# pic.net
KiCad netlist of a schematic drawn in Altium Designer
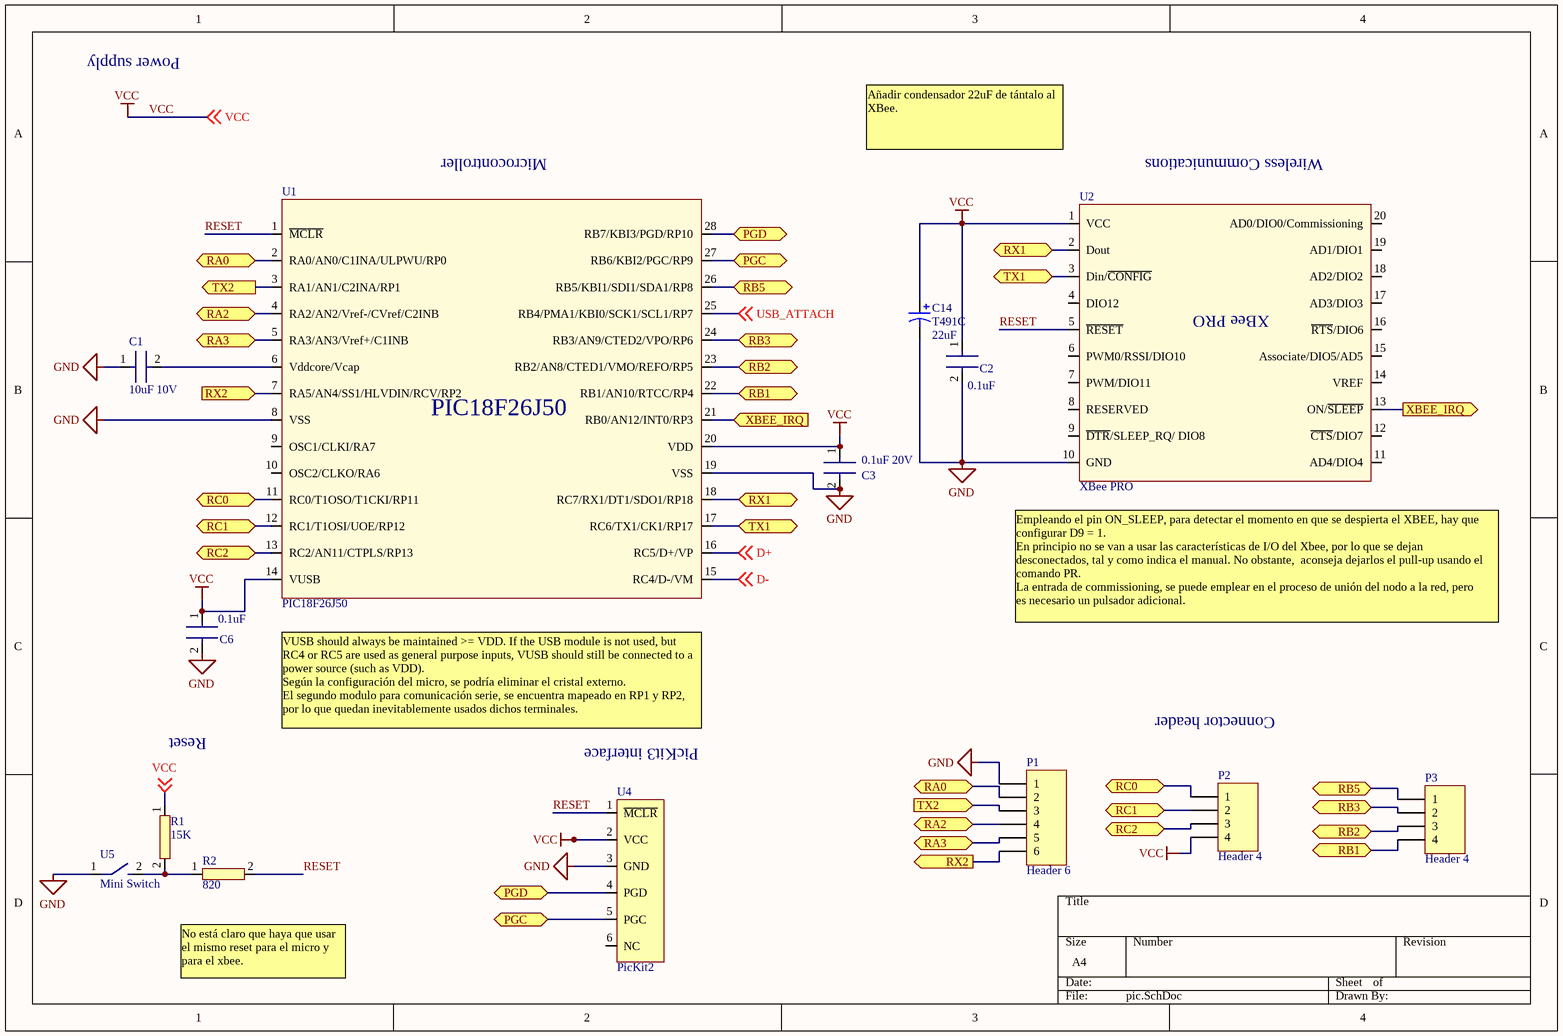
[diagram p0: pic.SchDoc]

(export (version "E")
  (design (tool "Eeschema 10.0.6"))
  (components
    (comp (ref "C1")
      (value "10uF 10V")
      (footprint "C1206")
      (libsource (lib "uMote") (part "TDK C3216X7R1C106K"))
    )
    (comp (ref "C2")
      (value "0.1uF")
      (footprint "C1206")
      (libsource (lib "uMote") (part "TDK C3216X7R1C106K"))
    )
    (comp (ref "C3")
      (value "0.1uF 20V")
      (footprint "C1206")
      (libsource (lib "uMote") (part "TDK C3216X7R1C106K"))
    )
    (comp (ref "C6")
      (value "0.1uF")
      (footprint "C1206")
      (libsource (lib "uMote") (part "TDK C3216X7R1C106K"))
    )
    (comp (ref "C14")
      (value "T491C")
      (footprint "C")
      (description "Solid Tantalum Chip Capacitor, Standard T491 Series - Industrial Grade")
      (fields (field (name "ALTIUM_VALUE") "22uF") (field (name "PUBLISHER") "Altium Limited"))
      (libsource (lib "KEMET Chip Capacitor") (part "T491C"))
    )
    (comp (ref "P1")
      (value "Header 6")
      (footprint "HDR1X6")
      (description "Header, 6-Pin")
      (fields (field (name "PUBLISHER") "Altium Limited"))
      (libsource (lib "Miscellaneous Connectors") (part "Header 6"))
    )
    (comp (ref "P2")
      (value "Header 4")
      (footprint "HDR1X4")
      (description "Header, 4-Pin")
      (fields (field (name "PUBLISHER") "Altium Limited"))
      (libsource (lib "Miscellaneous Connectors") (part "Header 4"))
    )
    (comp (ref "P3")
      (value "Header 4")
      (footprint "HDR1X4")
      (description "Header, 4-Pin")
      (fields (field (name "PUBLISHER") "Altium Limited"))
      (libsource (lib "Miscellaneous Connectors") (part "Header 4"))
    )
    (comp (ref "R1") (value "15K") (footprint "3216[1206]") (libsource (lib "uMote") (part "RES 1206")))
    (comp (ref "R2") (value "820") (footprint "3216[1206]") (libsource (lib "") (part "RES 1206_1")))
    (comp (ref "U1")
      (value "PIC18F26J50")
      (footprint "PIC18F-SOIC")
      (libsource (lib "uMote") (part "PIC18F26J50"))
    )
    (comp (ref "U2") (value "XBee PRO") (footprint "XBee PRO") (libsource (lib "uMote") (part "XBee PRO")))
    (comp (ref "U4") (value "PicKit2") (footprint "PICKIT3") (libsource (lib "uMote") (part "PicKit2")))
    (comp (ref "U5")
      (value "Mini Switch")
      (footprint "Mini Switch")
      (libsource (lib "uMote") (part "Mini Switch"))
    )
  )
  (nets
    (net (code "1") (name "/PGC") (class "Default")
      (node (ref "U1") (pin "27") (pinfunction "RB6/KBI2/PGC/RP9_27") (pintype "passive"))
      (node (ref "U4") (pin "5") (pinfunction "PGC_5") (pintype "passive"))
    )
    (net (code "2") (name "/PGD") (class "Default")
      (node (ref "U1") (pin "28") (pinfunction "RB7/KBI3/PGD/RP10_28") (pintype "passive"))
      (node (ref "U4") (pin "4") (pinfunction "PGD_4") (pintype "passive"))
    )
    (net (code "3") (name "/RA0") (class "Default")
      (node (ref "P1") (pin "2") (pinfunction "2_2") (pintype "passive"))
      (node (ref "U1") (pin "2") (pinfunction "RA0/AN0/C1INA/ULPWU/RP0_2") (pintype "passive"))
    )
    (net (code "4") (name "/RA2") (class "Default")
      (node (ref "P1") (pin "4") (pinfunction "4_4") (pintype "passive"))
      (node (ref "U1") (pin "4") (pinfunction "RA2/AN2/Vref-/CVref/C2INB_4") (pintype "passive"))
    )
    (net (code "5") (name "/RA3") (class "Default")
      (node (ref "P1") (pin "5") (pinfunction "5_5") (pintype "passive"))
      (node (ref "U1") (pin "5") (pinfunction "RA3/AN3/Vref+/C1INB_5") (pintype "passive"))
    )
    (net (code "6") (name "/RB1") (class "Default")
      (node (ref "P3") (pin "4") (pinfunction "4_4") (pintype "passive"))
      (node (ref "U1") (pin "22") (pinfunction "RB1/AN10/RTCC/RP4_22") (pintype "passive"))
    )
    (net (code "7") (name "/RB2") (class "Default")
      (node (ref "P3") (pin "3") (pinfunction "3_3") (pintype "passive"))
      (node (ref "U1") (pin "23") (pinfunction "RB2/AN8/CTED1/VMO/REFO/RP5_23") (pintype "passive"))
    )
    (net (code "8") (name "/RB3") (class "Default")
      (node (ref "P3") (pin "2") (pinfunction "2_2") (pintype "passive"))
      (node (ref "U1") (pin "24") (pinfunction "RB3/AN9/CTED2/VPO/RP6_24") (pintype "passive"))
    )
    (net (code "9") (name "/RB5") (class "Default")
      (node (ref "P3") (pin "1") (pinfunction "1_1") (pintype "passive"))
      (node (ref "U1") (pin "26") (pinfunction "RB5/KBI1/SDI1/SDA1/RP8_26") (pintype "passive"))
    )
    (net (code "10") (name "/RC0") (class "Default")
      (node (ref "P2") (pin "1") (pinfunction "1_1") (pintype "passive"))
      (node (ref "U1") (pin "11") (pinfunction "RC0/T1OSO/T1CKI/RP11_11") (pintype "passive"))
    )
    (net (code "11") (name "/RC1") (class "Default")
      (node (ref "P2") (pin "2") (pinfunction "2_2") (pintype "passive"))
      (node (ref "U1") (pin "12") (pinfunction "RC1/T1OSI/UOE/RP12_12") (pintype "passive"))
    )
    (net (code "12") (name "/RC2") (class "Default")
      (node (ref "P2") (pin "3") (pinfunction "3_3") (pintype "passive"))
      (node (ref "U1") (pin "13") (pinfunction "RC2/AN11/CTPLS/RP13_13") (pintype "passive"))
    )
    (net (code "13") (name "/RESET") (class "Default")
      (node (ref "R2") (pin "2") (pinfunction "2_2") (pintype "passive"))
      (node (ref "U1") (pin "1") (pinfunction "MCLR_1") (pintype "input"))
      (node (ref "U2") (pin "5") (pinfunction "RESET_5") (pintype "passive"))
      (node (ref "U4") (pin "1") (pinfunction "MCLR_1") (pintype "passive"))
    )
    (net (code "14") (name "/RX1") (class "Default")
      (node (ref "U1") (pin "18") (pinfunction "RC7/RX1/DT1/SDO1/RP18_18") (pintype "passive"))
      (node (ref "U2") (pin "2") (pinfunction "Dout_2") (pintype "passive"))
    )
    (net (code "15") (name "/RX2") (class "Default")
      (node (ref "P1") (pin "6") (pinfunction "6_6") (pintype "passive"))
      (node (ref "U1") (pin "7") (pinfunction "RA5/AN4/SS1/HLVDIN/RCV/RP2_7") (pintype "passive"))
    )
    (net (code "16") (name "/TX1") (class "Default")
      (node (ref "U1") (pin "17") (pinfunction "RC6/TX1/CK1/RP17_17") (pintype "passive"))
      (node (ref "U2") (pin "3") (pinfunction "Din/~{CONFIG}_3") (pintype "passive"))
    )
    (net (code "17") (name "/TX2") (class "Default")
      (node (ref "P1") (pin "3") (pinfunction "3_3") (pintype "passive"))
      (node (ref "U1") (pin "3") (pinfunction "RA1/AN1/C2INA/RP1_3") (pintype "passive"))
    )
    (net (code "18") (name "/XBEE_IRQ") (class "Default")
      (node (ref "U1") (pin "21") (pinfunction "RB0/AN12/INT0/RP3_21") (pintype "passive"))
      (node (ref "U2") (pin "13") (pinfunction "ON/~{SLEEP}_13") (pintype "passive"))
    )
    (net (code "19") (name "D+") (class "Default")
      (node (ref "U1") (pin "16") (pinfunction "RC5/D+/VP_16") (pintype "passive"))
    )
    (net (code "20") (name "D-") (class "Default")
      (node (ref "U1") (pin "15") (pinfunction "RC4/D-/VM_15") (pintype "passive"))
    )
    (net (code "21") (name "GND") (class "Default")
      (node (ref "C1") (pin "1") (pinfunction "1_1") (pintype "passive"))
      (node (ref "C14") (pin "2") (pinfunction "2_2") (pintype "passive"))
      (node (ref "C2") (pin "2") (pinfunction "2_2") (pintype "passive"))
      (node (ref "C3") (pin "2") (pinfunction "2_2") (pintype "passive"))
      (node (ref "C6") (pin "2") (pinfunction "2_2") (pintype "passive"))
      (node (ref "P1") (pin "1") (pinfunction "1_1") (pintype "passive"))
      (node (ref "U1") (pin "19") (pinfunction "VSS_19") (pintype "passive"))
      (node (ref "U1") (pin "8") (pinfunction "VSS_8") (pintype "passive"))
      (node (ref "U2") (pin "10") (pinfunction "GND_10") (pintype "passive"))
      (node (ref "U4") (pin "3") (pinfunction "GND_3") (pintype "passive"))
      (node (ref "U5") (pin "1") (pinfunction "1_1") (pintype "passive"))
    )
    (net (code "22") (name "Net-(R1-Pad2)") (class "Default")
      (node (ref "R1") (pin "2") (pinfunction "2_2") (pintype "passive"))
      (node (ref "R2") (pin "1") (pinfunction "1_1") (pintype "passive"))
      (node (ref "U5") (pin "2") (pinfunction "2_2") (pintype "passive"))
    )
    (net (code "23") (name "Net-(U1-Vddcore{slash}Vcap)") (class "Default")
      (node (ref "C1") (pin "2") (pinfunction "2_2") (pintype "passive"))
      (node (ref "U1") (pin "6") (pinfunction "Vddcore/Vcap_6") (pintype "passive"))
    )
    (net (code "24") (name "USB_ATTACH") (class "Default")
      (node (ref "U1") (pin "25") (pinfunction "RB4/PMA1/KBI0/SCK1/SCL1/RP7_25") (pintype "passive"))
    )
    (net (code "25") (name "VCC") (class "Default")
      (node (ref "C14") (pin "1") (pinfunction "1_1") (pintype "passive"))
      (node (ref "C2") (pin "1") (pinfunction "1_1") (pintype "passive"))
      (node (ref "C3") (pin "1") (pinfunction "1_1") (pintype "passive"))
      (node (ref "C6") (pin "1") (pinfunction "1_1") (pintype "passive"))
      (node (ref "P2") (pin "4") (pinfunction "4_4") (pintype "passive"))
      (node (ref "R1") (pin "1") (pinfunction "1_1") (pintype "passive"))
      (node (ref "U1") (pin "14") (pinfunction "VUSB_14") (pintype "passive"))
      (node (ref "U1") (pin "20") (pinfunction "VDD_20") (pintype "passive"))
      (node (ref "U2") (pin "1") (pinfunction "VCC_1") (pintype "passive"))
      (node (ref "U4") (pin "2") (pinfunction "VCC_2") (pintype "passive"))
    )
    (net (code "26") (name "unconnected-(U1-OSC1{slash}CLKI{slash}RA7-Pad9)") (class "Default")
      (node (ref "U1") (pin "9") (pinfunction "OSC1/CLKI/RA7_9") (pintype "passive"))
    )
    (net (code "27") (name "unconnected-(U1-OSC2{slash}CLKO{slash}RA6-Pad10)") (class "Default")
      (node (ref "U1") (pin "10") (pinfunction "OSC2/CLKO/RA6_10") (pintype "passive"))
    )
    (net (code "28") (name "unconnected-(U2-AD0{slash}DIO0{slash}Commissioning-Pad20)") (class "Default")
      (node (ref "U2") (pin "20") (pinfunction "AD0/DIO0/Commissioning_20") (pintype "passive"))
    )
    (net (code "29") (name "unconnected-(U2-AD1{slash}DIO1-Pad19)") (class "Default")
      (node (ref "U2") (pin "19") (pinfunction "AD1/DIO1_19") (pintype "passive"))
    )
    (net (code "30") (name "unconnected-(U2-AD2{slash}DIO2-Pad18)") (class "Default")
      (node (ref "U2") (pin "18") (pinfunction "AD2/DIO2_18") (pintype "passive"))
    )
    (net (code "31") (name "unconnected-(U2-AD3{slash}DIO3-Pad17)") (class "Default")
      (node (ref "U2") (pin "17") (pinfunction "AD3/DIO3_17") (pintype "passive"))
    )
    (net (code "32") (name "unconnected-(U2-AD4{slash}DIO4-Pad11)") (class "Default")
      (node (ref "U2") (pin "11") (pinfunction "AD4/DIO4_11") (pintype "passive"))
    )
    (net (code "33") (name "unconnected-(U2-Associate{slash}DIO5{slash}AD5-Pad15)") (class "Default")
      (node (ref "U2") (pin "15") (pinfunction "Associate/DIO5/AD5_15") (pintype "passive"))
    )
    (net (code "34") (name "unconnected-(U2-DIO12-Pad4)") (class "Default")
      (node (ref "U2") (pin "4") (pinfunction "DIO12_4") (pintype "passive"))
    )
    (net (code "35") (name "unconnected-(U2-PWM0{slash}RSSI{slash}DIO10-Pad6)") (class "Default")
      (node (ref "U2") (pin "6") (pinfunction "PWM0/RSSI/DIO10_6") (pintype "passive"))
    )
    (net (code "36") (name "unconnected-(U2-PWM{slash}DIO11-Pad7)") (class "Default")
      (node (ref "U2") (pin "7") (pinfunction "PWM/DIO11_7") (pintype "passive"))
    )
    (net (code "37") (name "unconnected-(U2-RESERVED-Pad8)") (class "Default")
      (node (ref "U2") (pin "8") (pinfunction "RESERVED_8") (pintype "passive"))
    )
    (net (code "38") (name "unconnected-(U2-VREF-Pad14)") (class "Default")
      (node (ref "U2") (pin "14") (pinfunction "VREF_14") (pintype "passive"))
    )
    (net (code "39") (name "unconnected-(U2-~{CTS}{slash}DIO7-Pad12)") (class "Default")
      (node (ref "U2") (pin "12") (pinfunction "~{CTS}/DIO7_12") (pintype "passive"))
    )
    (net (code "40") (name "unconnected-(U2-~{DTR}{slash}SLEEP_RQ{slash}_DIO8-Pad9)") (class "Default")
      (node (ref "U2") (pin "9") (pinfunction "~{DTR}/SLEEP_RQ/_DIO8_9") (pintype "passive"))
    )
    (net (code "41") (name "unconnected-(U2-~{RTS}{slash}DIO6-Pad16)") (class "Default")
      (node (ref "U2") (pin "16") (pinfunction "~{RTS}/DIO6_16") (pintype "passive"))
    )
    (net (code "42") (name "unconnected-(U4-NC-Pad6)") (class "Default")
      (node (ref "U4") (pin "6") (pinfunction "NC_6") (pintype "passive"))
    )
  )
)
